# motorEncoder.net
KiCad netlist of a schematic drawn in Altium Designer
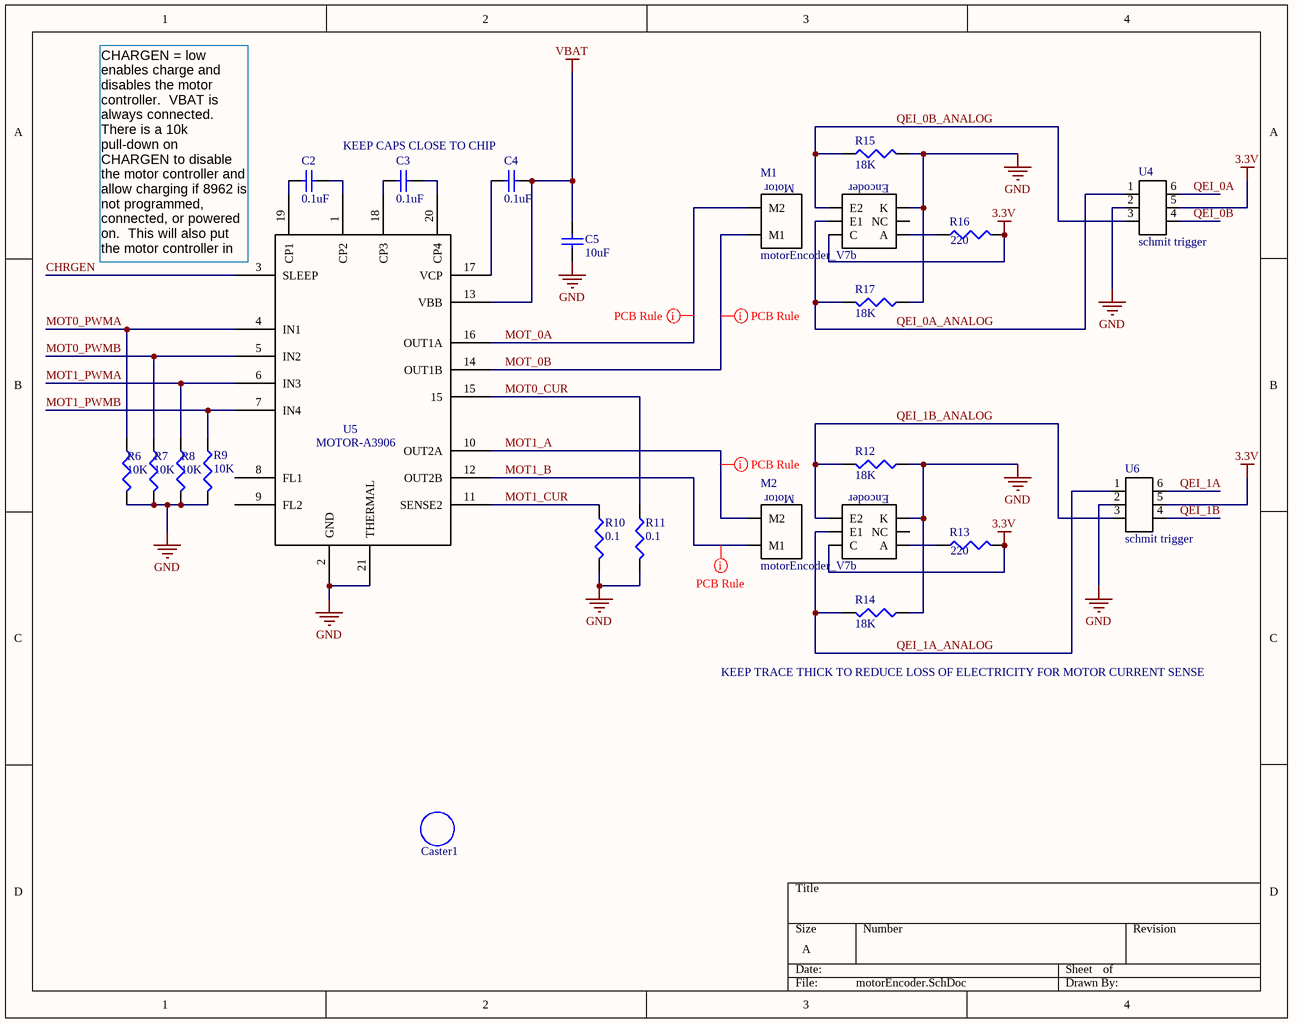
[diagram p0: motorEncoder.SchDoc]

(export (version "E")
  (design (tool "Eeschema 10.0.6"))
  (components
    (comp (ref "C2")
      (value "0.1uF")
      (footprint "CAPC1005L")
      (description "Capacitor (Semiconductor SIM Model)")
      (fields (field (name "Comment") "Cap Semi") (field (name "PUBLISHER") "Altium Limited"))
      (libsource (lib "Miscellaneous Devices") (part "Cap Semi"))
    )
    (comp (ref "C3")
      (value "0.1uF")
      (footprint "CAPC1005L")
      (description "Capacitor (Semiconductor SIM Model)")
      (fields (field (name "Comment") "Cap Semi") (field (name "PUBLISHER") "Altium Limited"))
      (libsource (lib "Miscellaneous Devices") (part "Cap Semi"))
    )
    (comp (ref "C4")
      (value "0.1uF")
      (footprint "CAPC1005L")
      (description "Capacitor (Semiconductor SIM Model)")
      (fields (field (name "Comment") "Cap Semi") (field (name "PUBLISHER") "Altium Limited"))
      (libsource (lib "Miscellaneous Devices") (part "Cap Semi"))
    )
    (comp (ref "C5")
      (value "10uF")
      (footprint "CAPC1608L")
      (description "Capacitor (Semiconductor SIM Model)")
      (fields (field (name "Comment") "Cap Semi") (field (name "PUBLISHER") "Altium Limited"))
      (libsource (lib "Miscellaneous Devices") (part "Cap Semi"))
    )
    (comp (ref "Caster1")
      (value "non connect")
      (footprint "3/4\"CASTER2")
      (description "This is just a space saver to get the caster onto the pcb")
      (libsource (lib "mrone") (part "Caster 3/4in"))
    )
    (comp (ref "M1")
      (value "motorEncoder_V7b")
      (footprint "motorEncoder_V7b")
      (libsource (lib "mrone") (part "motorEncoder_V7b"))
    )
    (comp (ref "M2")
      (value "motorEncoder_V7b")
      (footprint "motorEncoder_V7b")
      (libsource (lib "mrone") (part "motorEncoder_V7b"))
    )
    (comp (ref "R6")
      (value "10K")
      (footprint "RESC1608L")
      (description "Resistor")
      (fields (field (name "Comment") "Res3") (field (name "PUBLISHER") "Altium Limited"))
      (libsource (lib "Miscellaneous Devices") (part "Res3"))
    )
    (comp (ref "R7")
      (value "10K")
      (footprint "RESC1608L")
      (description "Resistor")
      (fields (field (name "Comment") "Res3") (field (name "PUBLISHER") "Altium Limited"))
      (libsource (lib "Miscellaneous Devices") (part "Res3"))
    )
    (comp (ref "R8")
      (value "10K")
      (footprint "RESC1608L")
      (description "Resistor")
      (fields (field (name "Comment") "Res3") (field (name "PUBLISHER") "Altium Limited"))
      (libsource (lib "Miscellaneous Devices") (part "Res3"))
    )
    (comp (ref "R9")
      (value "10K")
      (footprint "RESC1608L")
      (description "Resistor")
      (fields (field (name "Comment") "Res3") (field (name "PUBLISHER") "Altium Limited"))
      (libsource (lib "Miscellaneous Devices") (part "Res3"))
    )
    (comp (ref "R10")
      (value "0.1")
      (footprint "RESC1608L")
      (description "Resistor")
      (fields (field (name "Comment") "Res3") (field (name "PUBLISHER") "Altium Limited"))
      (libsource (lib "Miscellaneous Devices") (part "Res3"))
    )
    (comp (ref "R11")
      (value "0.1")
      (footprint "RESC1608L")
      (description "Resistor")
      (fields (field (name "Comment") "Res3") (field (name "PUBLISHER") "Altium Limited"))
      (libsource (lib "Miscellaneous Devices") (part "Res3"))
    )
    (comp (ref "R12")
      (value "18K")
      (footprint "RESC1608L")
      (description "Resistor")
      (fields (field (name "PUBLISHER") "Altium Limited"))
      (libsource (lib "Miscellaneous Devices") (part "Res3"))
    )
    (comp (ref "R13")
      (value "220")
      (footprint "RESC1608L")
      (description "Resistor")
      (fields (field (name "PUBLISHER") "Altium Limited"))
      (libsource (lib "Miscellaneous Devices") (part "Res3"))
    )
    (comp (ref "R14")
      (value "18K")
      (footprint "RESC1608L")
      (description "Resistor")
      (fields (field (name "PUBLISHER") "Altium Limited"))
      (libsource (lib "Miscellaneous Devices") (part "Res3"))
    )
    (comp (ref "R15")
      (value "18K")
      (footprint "RESC1608L")
      (description "Resistor")
      (fields (field (name "PUBLISHER") "Altium Limited"))
      (libsource (lib "Miscellaneous Devices") (part "Res3"))
    )
    (comp (ref "R16")
      (value "220")
      (footprint "RESC1608L")
      (description "Resistor")
      (fields (field (name "PUBLISHER") "Altium Limited"))
      (libsource (lib "Miscellaneous Devices") (part "Res3"))
    )
    (comp (ref "R17")
      (value "18K")
      (footprint "RESC1608L")
      (description "Resistor")
      (fields (field (name "PUBLISHER") "Altium Limited"))
      (libsource (lib "Miscellaneous Devices") (part "Res3"))
    )
    (comp (ref "U4")
      (value "schmit trigger")
      (footprint "DCK(R-PDSO-C6)")
      (libsource (lib "mrone") (part "schmit trigger"))
    )
    (comp (ref "U5")
      (value "MOTOR-A3906")
      (footprint "QFN-20")
      (libsource (lib "V2_altium") (part "MOTOR-A3906"))
    )
    (comp (ref "U6")
      (value "schmit trigger")
      (footprint "DCK(R-PDSO-C6)")
      (libsource (lib "mrone") (part "schmit trigger"))
    )
  )
  (nets
    (net (code "2") (name "/CHRGEN") (class "Default")
      (node (ref "U5") (pin "3") (pinfunction "SLEEP_3") (pintype "passive"))
    )
    (net (code "3") (name "/MOT0_CUR") (class "Default")
      (node (ref "R11") (pin "1") (pinfunction "1_1") (pintype "passive"))
      (node (ref "U5") (pin "15") (pinfunction "15_15") (pintype "passive"))
    )
    (net (code "4") (name "/MOT0_PWMA") (class "Default")
      (node (ref "R6") (pin "1") (pinfunction "1_1") (pintype "passive"))
      (node (ref "U5") (pin "4") (pinfunction "IN1_4") (pintype "passive"))
    )
    (net (code "5") (name "/MOT0_PWMB") (class "Default")
      (node (ref "R7") (pin "1") (pinfunction "1_1") (pintype "passive"))
      (node (ref "U5") (pin "5") (pinfunction "IN2_5") (pintype "passive"))
    )
    (net (code "6") (name "/MOT1_A") (class "Default")
      (node (ref "M2") (pin "M2") (pinfunction "M2_M2") (pintype "passive"))
      (node (ref "U5") (pin "10") (pinfunction "OUT2A_10") (pintype "passive"))
    )
    (net (code "7") (name "/MOT1_B") (class "Default")
      (node (ref "M2") (pin "M1") (pinfunction "M1_M1") (pintype "passive"))
      (node (ref "U5") (pin "12") (pinfunction "OUT2B_12") (pintype "passive"))
    )
    (net (code "8") (name "/MOT1_CUR") (class "Default")
      (node (ref "R10") (pin "1") (pinfunction "1_1") (pintype "passive"))
      (node (ref "U5") (pin "11") (pinfunction "SENSE2_11") (pintype "passive"))
    )
    (net (code "9") (name "/MOT1_PWMA") (class "Default")
      (node (ref "R8") (pin "1") (pinfunction "1_1") (pintype "passive"))
      (node (ref "U5") (pin "6") (pinfunction "IN3_6") (pintype "passive"))
    )
    (net (code "10") (name "/MOT1_PWMB") (class "Default")
      (node (ref "R9") (pin "1") (pinfunction "1_1") (pintype "passive"))
      (node (ref "U5") (pin "7") (pinfunction "IN4_7") (pintype "passive"))
    )
    (net (code "11") (name "/MOT_0A") (class "Default")
      (node (ref "M1") (pin "M2") (pinfunction "M2_M2") (pintype "passive"))
      (node (ref "U5") (pin "16") (pinfunction "OUT1A_16") (pintype "passive"))
    )
    (net (code "12") (name "/MOT_0B") (class "Default")
      (node (ref "M1") (pin "M1") (pinfunction "M1_M1") (pintype "passive"))
      (node (ref "U5") (pin "14") (pinfunction "OUT1B_14") (pintype "passive"))
    )
    (net (code "13") (name "/QEI_0A") (class "Default")
      (node (ref "U4") (pin "6") (pinfunction "4_6") (pintype "passive"))
    )
    (net (code "14") (name "/QEI_0A_ANALOG") (class "Default")
      (node (ref "M1") (pin "E1") (pinfunction "E1_E1") (pintype "passive"))
      (node (ref "R17") (pin "2") (pinfunction "2_2") (pintype "passive"))
      (node (ref "U4") (pin "1") (pinfunction "1_1") (pintype "passive"))
    )
    (net (code "15") (name "/QEI_0B") (class "Default")
      (node (ref "U4") (pin "4") (pinfunction "4_4") (pintype "passive"))
    )
    (net (code "16") (name "/QEI_0B_ANALOG") (class "Default")
      (node (ref "M1") (pin "E2") (pinfunction "E2_E2") (pintype "passive"))
      (node (ref "R15") (pin "1") (pinfunction "1_1") (pintype "passive"))
      (node (ref "U4") (pin "3") (pinfunction "3_3") (pintype "passive"))
    )
    (net (code "17") (name "/QEI_1A") (class "Default")
      (node (ref "U6") (pin "6") (pinfunction "4_6") (pintype "passive"))
    )
    (net (code "18") (name "/QEI_1A_ANALOG") (class "Default")
      (node (ref "M2") (pin "E1") (pinfunction "E1_E1") (pintype "passive"))
      (node (ref "R14") (pin "2") (pinfunction "2_2") (pintype "passive"))
      (node (ref "U6") (pin "1") (pinfunction "1_1") (pintype "passive"))
    )
    (net (code "19") (name "/QEI_1B") (class "Default")
      (node (ref "U6") (pin "4") (pinfunction "4_4") (pintype "passive"))
    )
    (net (code "20") (name "/QEI_1B_ANALOG") (class "Default")
      (node (ref "M2") (pin "E2") (pinfunction "E2_E2") (pintype "passive"))
      (node (ref "R12") (pin "2") (pinfunction "2_2") (pintype "passive"))
      (node (ref "U6") (pin "3") (pinfunction "3_3") (pintype "passive"))
    )
    (net (code "21") (name "3.3V") (class "Default")
      (node (ref "M1") (pin "C") (pinfunction "C_C") (pintype "passive"))
      (node (ref "M2") (pin "C") (pinfunction "C_C") (pintype "passive"))
      (node (ref "R13") (pin "2") (pinfunction "2_2") (pintype "passive"))
      (node (ref "R16") (pin "2") (pinfunction "2_2") (pintype "passive"))
      (node (ref "U4") (pin "5") (pinfunction "5_5") (pintype "passive"))
      (node (ref "U6") (pin "5") (pinfunction "5_5") (pintype "passive"))
    )
    (net (code "22") (name "GND") (class "Default")
      (node (ref "C5") (pin "1") (pinfunction "1_1") (pintype "passive"))
      (node (ref "M1") (pin "K") (pinfunction "K_K") (pintype "passive"))
      (node (ref "M2") (pin "K") (pinfunction "K_K") (pintype "passive"))
      (node (ref "R10") (pin "2") (pinfunction "2_2") (pintype "passive"))
      (node (ref "R11") (pin "2") (pinfunction "2_2") (pintype "passive"))
      (node (ref "R12") (pin "1") (pinfunction "1_1") (pintype "passive"))
      (node (ref "R14") (pin "1") (pinfunction "1_1") (pintype "passive"))
      (node (ref "R15") (pin "2") (pinfunction "2_2") (pintype "passive"))
      (node (ref "R17") (pin "1") (pinfunction "1_1") (pintype "passive"))
      (node (ref "R6") (pin "2") (pinfunction "2_2") (pintype "passive"))
      (node (ref "R7") (pin "2") (pinfunction "2_2") (pintype "passive"))
      (node (ref "R8") (pin "2") (pinfunction "2_2") (pintype "passive"))
      (node (ref "R9") (pin "2") (pinfunction "2_2") (pintype "passive"))
      (node (ref "U4") (pin "2") (pinfunction "2_2") (pintype "passive"))
      (node (ref "U5") (pin "2") (pinfunction "GND_2") (pintype "passive"))
      (node (ref "U5") (pin "21") (pinfunction "THERMAL_21") (pintype "passive"))
      (node (ref "U6") (pin "2") (pinfunction "2_2") (pintype "passive"))
    )
    (net (code "23") (name "Net-(M1-PadA)") (class "Default")
      (node (ref "M1") (pin "A") (pinfunction "A_A") (pintype "passive"))
      (node (ref "R16") (pin "1") (pinfunction "1_1") (pintype "passive"))
    )
    (net (code "24") (name "Net-(M2-PadA)") (class "Default")
      (node (ref "M2") (pin "A") (pinfunction "A_A") (pintype "passive"))
      (node (ref "R13") (pin "1") (pinfunction "1_1") (pintype "passive"))
    )
    (net (code "25") (name "Net-(U5-CP1)") (class "Default")
      (node (ref "C2") (pin "1") (pinfunction "1_1") (pintype "passive"))
      (node (ref "U5") (pin "19") (pinfunction "CP1_19") (pintype "passive"))
    )
    (net (code "26") (name "Net-(U5-CP2)") (class "Default")
      (node (ref "C2") (pin "2") (pinfunction "2_2") (pintype "passive"))
      (node (ref "U5") (pin "1") (pinfunction "CP2_1") (pintype "passive"))
    )
    (net (code "27") (name "Net-(U5-CP3)") (class "Default")
      (node (ref "C3") (pin "1") (pinfunction "1_1") (pintype "passive"))
      (node (ref "U5") (pin "18") (pinfunction "CP3_18") (pintype "passive"))
    )
    (net (code "28") (name "Net-(U5-CP4)") (class "Default")
      (node (ref "C3") (pin "2") (pinfunction "2_2") (pintype "passive"))
      (node (ref "U5") (pin "20") (pinfunction "CP4_20") (pintype "passive"))
    )
    (net (code "29") (name "Net-(U5-VCP)") (class "Default")
      (node (ref "C4") (pin "2") (pinfunction "2_2") (pintype "passive"))
      (node (ref "U5") (pin "17") (pinfunction "VCP_17") (pintype "passive"))
    )
    (net (code "30") (name "VBAT") (class "Default")
      (node (ref "C4") (pin "1") (pinfunction "1_1") (pintype "passive"))
      (node (ref "C5") (pin "2") (pinfunction "2_2") (pintype "passive"))
      (node (ref "U5") (pin "13") (pinfunction "VBB_13") (pintype "passive"))
    )
    (net (code "31") (name "unconnected-(M1-PadNC)") (class "Default")
      (node (ref "M1") (pin "NC") (pinfunction "NC_NC") (pintype "passive"))
    )
    (net (code "32") (name "unconnected-(M2-PadNC)") (class "Default")
      (node (ref "M2") (pin "NC") (pinfunction "NC_NC") (pintype "passive"))
    )
    (net (code "33") (name "unconnected-(U5-FL1-Pad8)") (class "Default")
      (node (ref "U5") (pin "8") (pinfunction "FL1_8") (pintype "passive"))
    )
    (net (code "34") (name "unconnected-(U5-FL2-Pad9)") (class "Default")
      (node (ref "U5") (pin "9") (pinfunction "FL2_9") (pintype "passive"))
    )
  )
)
